# Stepper_Motor_Driver.net
KiCad netlist of a schematic drawn in Altium Designer
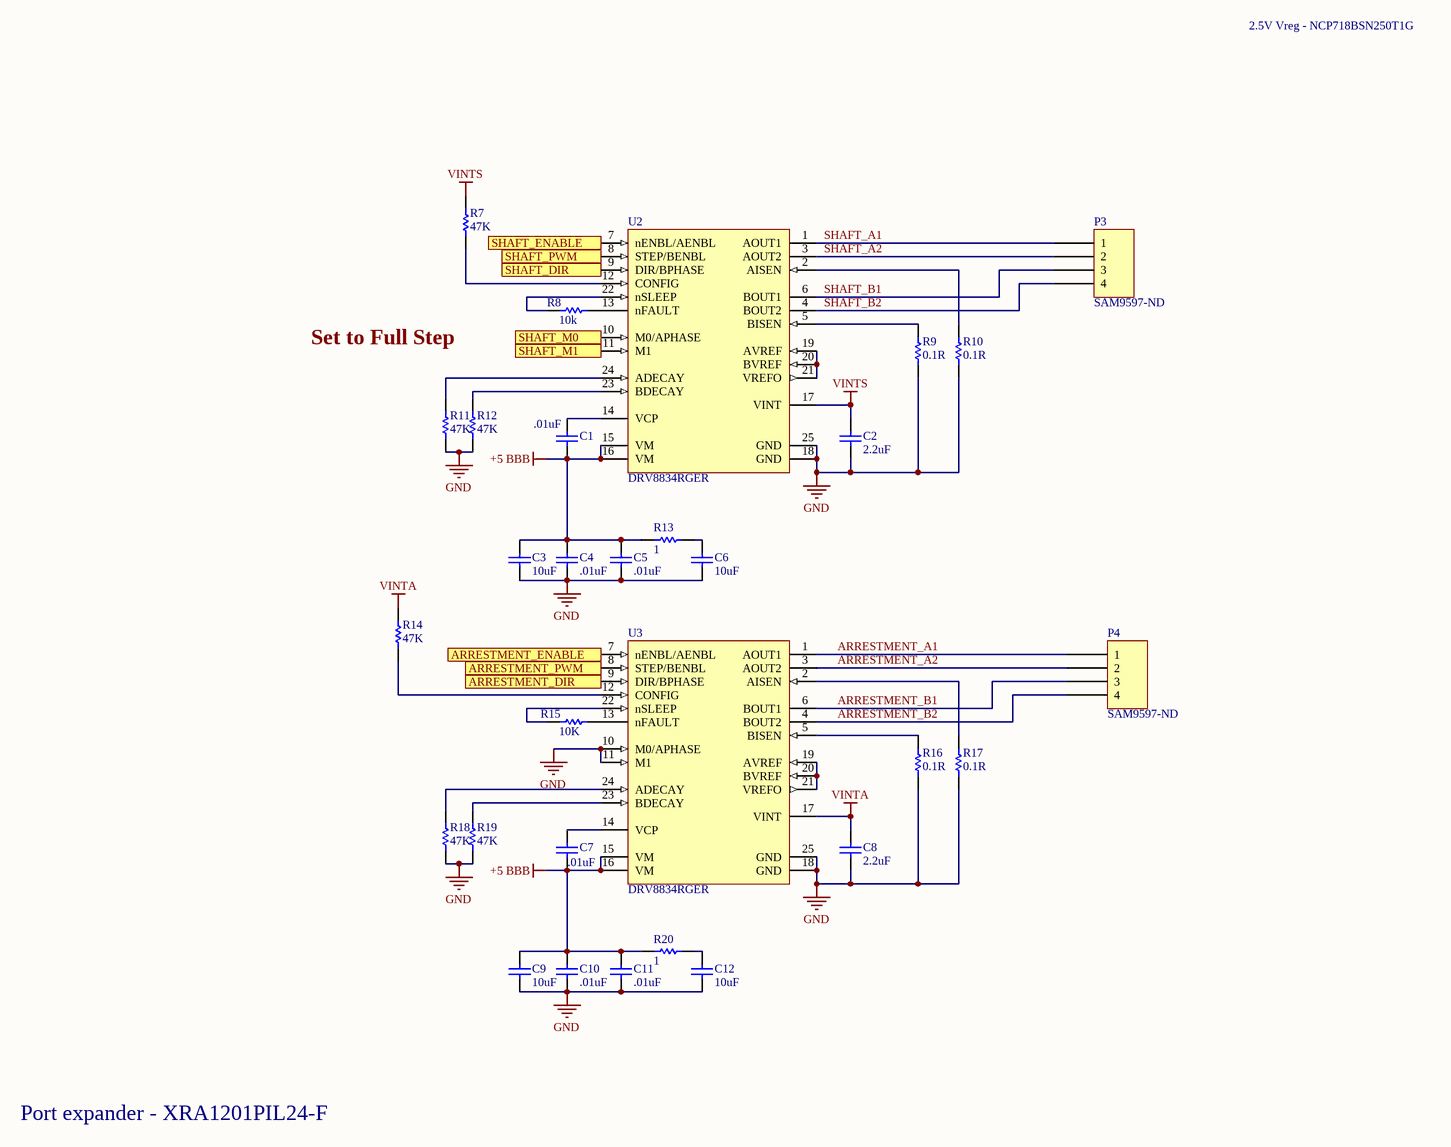
[diagram p0: Stepper Motor Driver.SchDoc]

(export (version "E")
  (design (tool "Eeschema 10.0.6"))
  (components
    (comp (ref "C1")
      (value ".01uF")
      (footprint "CAPC0402(1005)60_N")
      (description "CAP 220pF 25V ±10% 0402 (1005 Metric) Thickness 0.6mm SMD")
      (libsource (lib "Altium Content Vault") (part "CMP-1034-01365-1"))
    )
    (comp (ref "C2")
      (value "2.2uF")
      (footprint "CAPC0402(1005)60_N")
      (description "CAP 220pF 25V ±10% 0402 (1005 Metric) Thickness 0.6mm SMD")
      (libsource (lib "Altium Content Vault") (part "CMP-1034-01365-1"))
    )
    (comp (ref "C3")
      (value "10uF")
      (footprint "CAPC0402(1005)60_N")
      (description "CAP 220pF 25V ±10% 0402 (1005 Metric) Thickness 0.6mm SMD")
      (libsource (lib "Altium Content Vault") (part "CMP-1034-01365-1"))
    )
    (comp (ref "C4")
      (value ".01uF")
      (footprint "CAPC0402(1005)60_N")
      (description "CAP 220pF 25V ±10% 0402 (1005 Metric) Thickness 0.6mm SMD")
      (libsource (lib "Altium Content Vault") (part "CMP-1034-01365-1"))
    )
    (comp (ref "C5")
      (value ".01uF")
      (footprint "CAPC0402(1005)60_N")
      (description "CAP 220pF 25V ±10% 0402 (1005 Metric) Thickness 0.6mm SMD")
      (libsource (lib "Altium Content Vault") (part "CMP-1034-01365-1"))
    )
    (comp (ref "C6")
      (value "10uF")
      (footprint "CAPC0402(1005)60_N")
      (description "CAP 220pF 25V ±10% 0402 (1005 Metric) Thickness 0.6mm SMD")
      (libsource (lib "Altium Content Vault") (part "CMP-1034-01365-1"))
    )
    (comp (ref "C7")
      (value ".01uF")
      (footprint "CAPC0402(1005)60_N")
      (description "CAP 220pF 25V ±10% 0402 (1005 Metric) Thickness 0.6mm SMD")
      (libsource (lib "Altium Content Vault") (part "CMP-1034-01365-1"))
    )
    (comp (ref "C8")
      (value "2.2uF")
      (footprint "CAPC0402(1005)60_N")
      (description "CAP 220pF 25V ±10% 0402 (1005 Metric) Thickness 0.6mm SMD")
      (libsource (lib "Altium Content Vault") (part "CMP-1034-01365-1"))
    )
    (comp (ref "C9")
      (value "10uF")
      (footprint "CAPC0402(1005)60_N")
      (description "CAP 220pF 25V ±10% 0402 (1005 Metric) Thickness 0.6mm SMD")
      (libsource (lib "Altium Content Vault") (part "CMP-1034-01365-1"))
    )
    (comp (ref "C10")
      (value ".01uF")
      (footprint "CAPC0402(1005)60_N")
      (description "CAP 220pF 25V ±10% 0402 (1005 Metric) Thickness 0.6mm SMD")
      (libsource (lib "Altium Content Vault") (part "CMP-1034-01365-1"))
    )
    (comp (ref "C11")
      (value ".01uF")
      (footprint "CAPC0402(1005)60_N")
      (description "CAP 220pF 25V ±10% 0402 (1005 Metric) Thickness 0.6mm SMD")
      (libsource (lib "Altium Content Vault") (part "CMP-1034-01365-1"))
    )
    (comp (ref "C12")
      (value "10uF")
      (footprint "CAPC0402(1005)60_N")
      (description "CAP 220pF 25V ±10% 0402 (1005 Metric) Thickness 0.6mm SMD")
      (libsource (lib "Altium Content Vault") (part "CMP-1034-01365-1"))
    )
    (comp (ref "P3")
      (value "IPL1-104-01-L-S-RA-K")
      (footprint "IPL1-104-01-L-S-RA-K")
      (fields (field (name "SUPPLIER PART NUMBER 1") "SAM9597-ND"))
      (libsource (lib "ZLS_Schematic_lib") (part "IPL1-104-01-L-S-RA-K"))
    )
    (comp (ref "P4")
      (value "IPL1-104-01-L-S-RA-K")
      (footprint "IPL1-104-01-L-S-RA-K")
      (fields (field (name "SUPPLIER PART NUMBER 1") "SAM9597-ND"))
      (libsource (lib "ZLS_Schematic_lib") (part "IPL1-104-01-L-S-RA-K"))
    )
    (comp (ref "R7")
      (value "47K")
      (footprint "RESC0402(1005)_M")
      (libsource (lib "Altium Content Vault") (part "CMP-1011-00463-1"))
    )
    (comp (ref "R8")
      (value "10k")
      (footprint "RESC0402(1005)_M")
      (libsource (lib "Altium Content Vault") (part "CMP-1011-00463-1"))
    )
    (comp (ref "R9")
      (value "0.1R")
      (footprint "RESC0402(1005)_M")
      (libsource (lib "Altium Content Vault") (part "CMP-1011-00463-1"))
    )
    (comp (ref "R10")
      (value "0.1R")
      (footprint "RESC0402(1005)_M")
      (libsource (lib "Altium Content Vault") (part "CMP-1011-00463-1"))
    )
    (comp (ref "R11")
      (value "47K")
      (footprint "RESC0402(1005)_M")
      (libsource (lib "Altium Content Vault") (part "CMP-1011-00463-1"))
    )
    (comp (ref "R12")
      (value "47K")
      (footprint "RESC0402(1005)_M")
      (libsource (lib "Altium Content Vault") (part "CMP-1011-00463-1"))
    )
    (comp (ref "R13")
      (value "1")
      (footprint "RESC0402(1005)_M")
      (libsource (lib "Altium Content Vault") (part "CMP-1011-00463-1"))
    )
    (comp (ref "R14")
      (value "47K")
      (footprint "RESC0402(1005)_M")
      (libsource (lib "Altium Content Vault") (part "CMP-1011-00463-1"))
    )
    (comp (ref "R15")
      (value "10K")
      (footprint "RESC0402(1005)_M")
      (libsource (lib "Altium Content Vault") (part "CMP-1011-00463-1"))
    )
    (comp (ref "R16")
      (value "0.1R")
      (footprint "RESC0402(1005)_M")
      (libsource (lib "Altium Content Vault") (part "CMP-1011-00463-1"))
    )
    (comp (ref "R17")
      (value "0.1R")
      (footprint "RESC0402(1005)_M")
      (libsource (lib "Altium Content Vault") (part "CMP-1011-00463-1"))
    )
    (comp (ref "R18")
      (value "47K")
      (footprint "RESC0402(1005)_M")
      (libsource (lib "Altium Content Vault") (part "CMP-1011-00463-1"))
    )
    (comp (ref "R19")
      (value "47K")
      (footprint "RESC0402(1005)_M")
      (libsource (lib "Altium Content Vault") (part "CMP-1011-00463-1"))
    )
    (comp (ref "R20")
      (value "1")
      (footprint "RESC0402(1005)_M")
      (libsource (lib "Altium Content Vault") (part "CMP-1011-00463-1"))
    )
    (comp (ref "U2")
      (value "DRV8834RGER")
      (footprint "RGE0024B_V")
      (libsource (lib "Altium Content Vault") (part "TI-DRV8834RGE-24"))
    )
    (comp (ref "U3")
      (value "DRV8834RGER")
      (footprint "RGE0024B_V")
      (libsource (lib "Altium Content Vault") (part "TI-DRV8834RGE-24"))
    )
  )
  (nets
    (net (code "1") (name "+5 BBB") (class "Default")
      (node (ref "C1") (pin "1") (pinfunction "1_1") (pintype "passive"))
      (node (ref "C10") (pin "2") (pinfunction "2_2") (pintype "passive"))
      (node (ref "C11") (pin "2") (pinfunction "2_2") (pintype "passive"))
      (node (ref "C3") (pin "2") (pinfunction "2_2") (pintype "passive"))
      (node (ref "C4") (pin "2") (pinfunction "2_2") (pintype "passive"))
      (node (ref "C5") (pin "2") (pinfunction "2_2") (pintype "passive"))
      (node (ref "C7") (pin "1") (pinfunction "1_1") (pintype "passive"))
      (node (ref "C9") (pin "2") (pinfunction "2_2") (pintype "passive"))
      (node (ref "R13") (pin "1") (pinfunction "1_1") (pintype "passive"))
      (node (ref "R20") (pin "1") (pinfunction "1_1") (pintype "passive"))
      (node (ref "U2") (pin "15") (pinfunction "VM_15") (pintype "power_in"))
      (node (ref "U2") (pin "16") (pinfunction "VM_16") (pintype "power_in"))
      (node (ref "U3") (pin "15") (pinfunction "VM_15") (pintype "power_in"))
      (node (ref "U3") (pin "16") (pinfunction "VM_16") (pintype "power_in"))
    )
    (net (code "2") (name "/ARRESTMENT_A1") (class "Default")
      (node (ref "P4") (pin "1") (pinfunction "1_1") (pintype "passive"))
      (node (ref "U3") (pin "1") (pinfunction "AOUT1_1") (pintype "tri_state"))
    )
    (net (code "3") (name "/ARRESTMENT_A2") (class "Default")
      (node (ref "P4") (pin "2") (pinfunction "2_2") (pintype "passive"))
      (node (ref "U3") (pin "3") (pinfunction "AOUT2_3") (pintype "tri_state"))
    )
    (net (code "4") (name "/ARRESTMENT_B1") (class "Default")
      (node (ref "P4") (pin "3") (pinfunction "3_3") (pintype "passive"))
      (node (ref "U3") (pin "6") (pinfunction "BOUT1_6") (pintype "tri_state"))
    )
    (net (code "5") (name "/ARRESTMENT_B2") (class "Default")
      (node (ref "P4") (pin "4") (pinfunction "4_4") (pintype "passive"))
      (node (ref "U3") (pin "4") (pinfunction "BOUT2_4") (pintype "tri_state"))
    )
    (net (code "6") (name "/ARRESTMENT_DIR") (class "Default")
      (node (ref "U3") (pin "9") (pinfunction "DIR/BPHASE_9") (pintype "input"))
    )
    (net (code "7") (name "/ARRESTMENT_ENABLE") (class "Default")
      (node (ref "U3") (pin "7") (pinfunction "nENBL/AENBL_7") (pintype "input"))
    )
    (net (code "8") (name "/ARRESTMENT_PWM") (class "Default")
      (node (ref "U3") (pin "8") (pinfunction "STEP/BENBL_8") (pintype "input"))
    )
    (net (code "9") (name "/SHAFT_A1") (class "Default")
      (node (ref "P3") (pin "1") (pinfunction "1_1") (pintype "passive"))
      (node (ref "U2") (pin "1") (pinfunction "AOUT1_1") (pintype "tri_state"))
    )
    (net (code "10") (name "/SHAFT_A2") (class "Default")
      (node (ref "P3") (pin "2") (pinfunction "2_2") (pintype "passive"))
      (node (ref "U2") (pin "3") (pinfunction "AOUT2_3") (pintype "tri_state"))
    )
    (net (code "11") (name "/SHAFT_B1") (class "Default")
      (node (ref "P3") (pin "3") (pinfunction "3_3") (pintype "passive"))
      (node (ref "U2") (pin "6") (pinfunction "BOUT1_6") (pintype "tri_state"))
    )
    (net (code "12") (name "/SHAFT_B2") (class "Default")
      (node (ref "P3") (pin "4") (pinfunction "4_4") (pintype "passive"))
      (node (ref "U2") (pin "4") (pinfunction "BOUT2_4") (pintype "tri_state"))
    )
    (net (code "13") (name "/SHAFT_DIR") (class "Default")
      (node (ref "U2") (pin "9") (pinfunction "DIR/BPHASE_9") (pintype "input"))
    )
    (net (code "14") (name "/SHAFT_ENABLE") (class "Default")
      (node (ref "U2") (pin "7") (pinfunction "nENBL/AENBL_7") (pintype "input"))
    )
    (net (code "15") (name "/SHAFT_M0") (class "Default")
      (node (ref "U2") (pin "10") (pinfunction "M0/APHASE_10") (pintype "input"))
    )
    (net (code "16") (name "/SHAFT_M1") (class "Default")
      (node (ref "U2") (pin "11") (pinfunction "M1_11") (pintype "input"))
    )
    (net (code "17") (name "/SHAFT_PWM") (class "Default")
      (node (ref "U2") (pin "8") (pinfunction "STEP/BENBL_8") (pintype "input"))
    )
    (net (code "18") (name "GND") (class "Default")
      (node (ref "C10") (pin "1") (pinfunction "1_1") (pintype "passive"))
      (node (ref "C11") (pin "1") (pinfunction "1_1") (pintype "passive"))
      (node (ref "C12") (pin "1") (pinfunction "1_1") (pintype "passive"))
      (node (ref "C2") (pin "1") (pinfunction "1_1") (pintype "passive"))
      (node (ref "C3") (pin "1") (pinfunction "1_1") (pintype "passive"))
      (node (ref "C4") (pin "1") (pinfunction "1_1") (pintype "passive"))
      (node (ref "C5") (pin "1") (pinfunction "1_1") (pintype "passive"))
      (node (ref "C6") (pin "1") (pinfunction "1_1") (pintype "passive"))
      (node (ref "C8") (pin "1") (pinfunction "1_1") (pintype "passive"))
      (node (ref "C9") (pin "1") (pinfunction "1_1") (pintype "passive"))
      (node (ref "R10") (pin "2") (pinfunction "2_2") (pintype "passive"))
      (node (ref "R11") (pin "2") (pinfunction "2_2") (pintype "passive"))
      (node (ref "R12") (pin "2") (pinfunction "2_2") (pintype "passive"))
      (node (ref "R16") (pin "2") (pinfunction "2_2") (pintype "passive"))
      (node (ref "R17") (pin "2") (pinfunction "2_2") (pintype "passive"))
      (node (ref "R18") (pin "2") (pinfunction "2_2") (pintype "passive"))
      (node (ref "R19") (pin "2") (pinfunction "2_2") (pintype "passive"))
      (node (ref "R9") (pin "2") (pinfunction "2_2") (pintype "passive"))
      (node (ref "U2") (pin "18") (pinfunction "GND_18") (pintype "power_in"))
      (node (ref "U2") (pin "25") (pinfunction "GND_25") (pintype "power_in"))
      (node (ref "U3") (pin "10") (pinfunction "M0/APHASE_10") (pintype "input"))
      (node (ref "U3") (pin "11") (pinfunction "M1_11") (pintype "input"))
      (node (ref "U3") (pin "18") (pinfunction "GND_18") (pintype "power_in"))
      (node (ref "U3") (pin "25") (pinfunction "GND_25") (pintype "power_in"))
    )
    (net (code "19") (name "Net-(C6-Pad2)") (class "Default")
      (node (ref "C6") (pin "2") (pinfunction "2_2") (pintype "passive"))
      (node (ref "R13") (pin "2") (pinfunction "2_2") (pintype "passive"))
    )
    (net (code "20") (name "Net-(C12-Pad2)") (class "Default")
      (node (ref "C12") (pin "2") (pinfunction "2_2") (pintype "passive"))
      (node (ref "R20") (pin "2") (pinfunction "2_2") (pintype "passive"))
    )
    (net (code "21") (name "Net-(U2-ADECAY)") (class "Default")
      (node (ref "R11") (pin "1") (pinfunction "1_1") (pintype "passive"))
      (node (ref "U2") (pin "24") (pinfunction "ADECAY_24") (pintype "input"))
    )
    (net (code "22") (name "Net-(U2-AISEN)") (class "Default")
      (node (ref "R10") (pin "1") (pinfunction "1_1") (pintype "passive"))
      (node (ref "U2") (pin "2") (pinfunction "AISEN_2") (pintype "input"))
    )
    (net (code "23") (name "Net-(U2-AVREF)") (class "Default")
      (node (ref "U2") (pin "19") (pinfunction "AVREF_19") (pintype "input"))
      (node (ref "U2") (pin "20") (pinfunction "BVREF_20") (pintype "input"))
      (node (ref "U2") (pin "21") (pinfunction "VREFO_21") (pintype "output"))
    )
    (net (code "24") (name "Net-(U2-BDECAY)") (class "Default")
      (node (ref "R12") (pin "1") (pinfunction "1_1") (pintype "passive"))
      (node (ref "U2") (pin "23") (pinfunction "BDECAY_23") (pintype "input"))
    )
    (net (code "25") (name "Net-(U2-BISEN)") (class "Default")
      (node (ref "R9") (pin "1") (pinfunction "1_1") (pintype "passive"))
      (node (ref "U2") (pin "5") (pinfunction "BISEN_5") (pintype "input"))
    )
    (net (code "26") (name "Net-(U2-CONFIG)") (class "Default")
      (node (ref "R7") (pin "2") (pinfunction "2_2") (pintype "passive"))
      (node (ref "U2") (pin "12") (pinfunction "CONFIG_12") (pintype "input"))
    )
    (net (code "27") (name "Net-(U2-VCP)") (class "Default")
      (node (ref "C1") (pin "2") (pinfunction "2_2") (pintype "passive"))
      (node (ref "U2") (pin "14") (pinfunction "VCP_14") (pintype "passive"))
    )
    (net (code "28") (name "Net-(U2-nFAULT)") (class "Default")
      (node (ref "R8") (pin "2") (pinfunction "2_2") (pintype "passive"))
      (node (ref "U2") (pin "13") (pinfunction "nFAULT_13") (pintype "open_collector"))
    )
    (net (code "29") (name "Net-(U2-nSLEEP)") (class "Default")
      (node (ref "R8") (pin "1") (pinfunction "1_1") (pintype "passive"))
      (node (ref "U2") (pin "22") (pinfunction "nSLEEP_22") (pintype "input"))
    )
    (net (code "30") (name "Net-(U3-ADECAY)") (class "Default")
      (node (ref "R18") (pin "1") (pinfunction "1_1") (pintype "passive"))
      (node (ref "U3") (pin "24") (pinfunction "ADECAY_24") (pintype "input"))
    )
    (net (code "31") (name "Net-(U3-AISEN)") (class "Default")
      (node (ref "R17") (pin "1") (pinfunction "1_1") (pintype "passive"))
      (node (ref "U3") (pin "2") (pinfunction "AISEN_2") (pintype "input"))
    )
    (net (code "32") (name "Net-(U3-AVREF)") (class "Default")
      (node (ref "U3") (pin "19") (pinfunction "AVREF_19") (pintype "input"))
      (node (ref "U3") (pin "20") (pinfunction "BVREF_20") (pintype "input"))
      (node (ref "U3") (pin "21") (pinfunction "VREFO_21") (pintype "output"))
    )
    (net (code "33") (name "Net-(U3-BDECAY)") (class "Default")
      (node (ref "R19") (pin "1") (pinfunction "1_1") (pintype "passive"))
      (node (ref "U3") (pin "23") (pinfunction "BDECAY_23") (pintype "input"))
    )
    (net (code "34") (name "Net-(U3-BISEN)") (class "Default")
      (node (ref "R16") (pin "1") (pinfunction "1_1") (pintype "passive"))
      (node (ref "U3") (pin "5") (pinfunction "BISEN_5") (pintype "input"))
    )
    (net (code "35") (name "Net-(U3-CONFIG)") (class "Default")
      (node (ref "R14") (pin "2") (pinfunction "2_2") (pintype "passive"))
      (node (ref "U3") (pin "12") (pinfunction "CONFIG_12") (pintype "input"))
    )
    (net (code "36") (name "Net-(U3-VCP)") (class "Default")
      (node (ref "C7") (pin "2") (pinfunction "2_2") (pintype "passive"))
      (node (ref "U3") (pin "14") (pinfunction "VCP_14") (pintype "passive"))
    )
    (net (code "37") (name "Net-(U3-nFAULT)") (class "Default")
      (node (ref "R15") (pin "2") (pinfunction "2_2") (pintype "passive"))
      (node (ref "U3") (pin "13") (pinfunction "nFAULT_13") (pintype "open_collector"))
    )
    (net (code "38") (name "Net-(U3-nSLEEP)") (class "Default")
      (node (ref "R15") (pin "1") (pinfunction "1_1") (pintype "passive"))
      (node (ref "U3") (pin "22") (pinfunction "nSLEEP_22") (pintype "input"))
    )
    (net (code "39") (name "VINTA") (class "Default")
      (node (ref "C8") (pin "2") (pinfunction "2_2") (pintype "passive"))
      (node (ref "R14") (pin "1") (pinfunction "1_1") (pintype "passive"))
      (node (ref "U3") (pin "17") (pinfunction "VINT_17") (pintype "passive"))
    )
    (net (code "40") (name "VINTS") (class "Default")
      (node (ref "C2") (pin "2") (pinfunction "2_2") (pintype "passive"))
      (node (ref "R7") (pin "1") (pinfunction "1_1") (pintype "passive"))
      (node (ref "U2") (pin "17") (pinfunction "VINT_17") (pintype "passive"))
    )
  )
)
